# communication_module_20190819_to_aj-doy.net
KiCad netlist of a schematic drawn in EAGLE
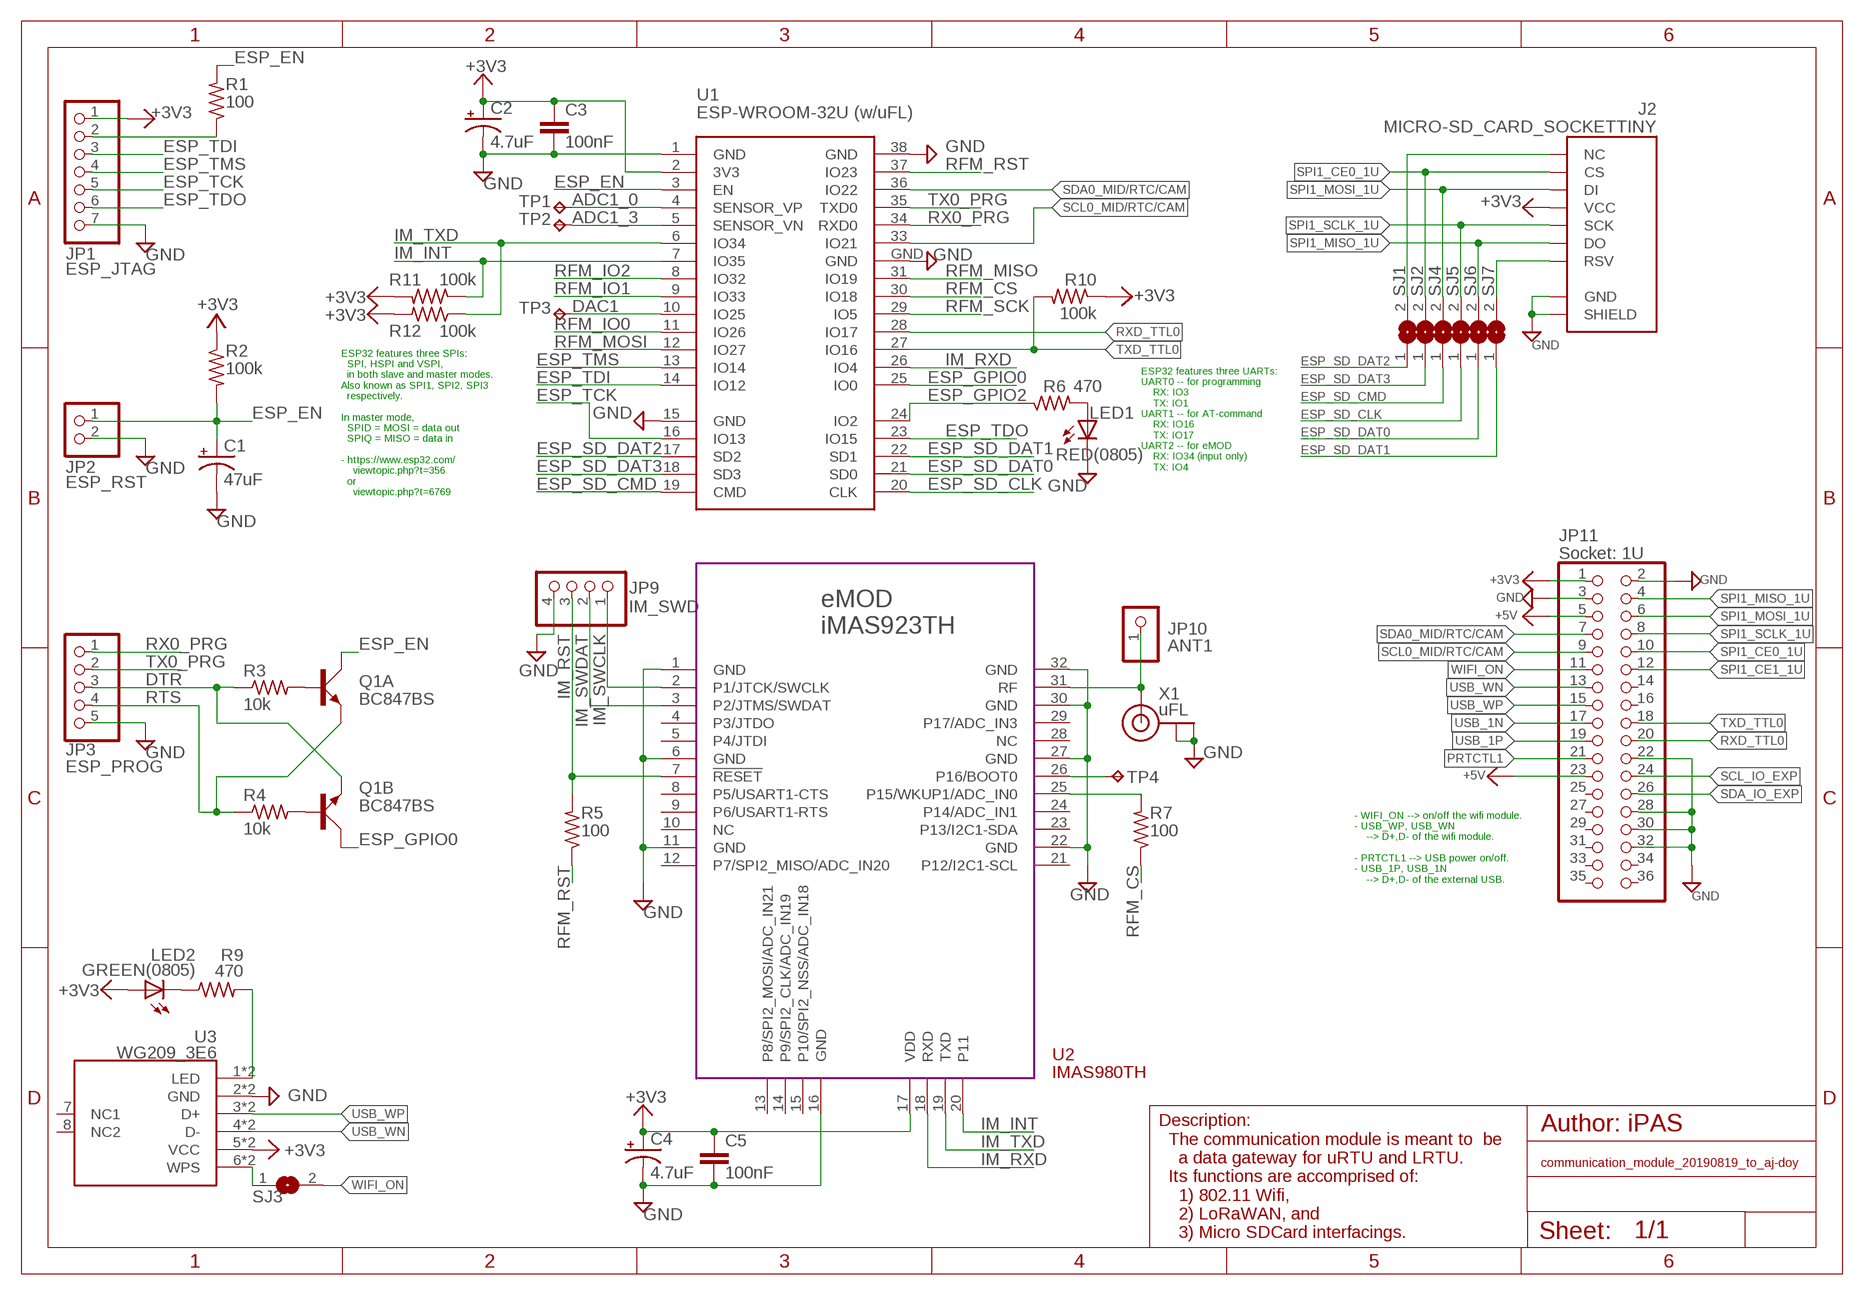
[diagram p0: schematic, sheet 1]

(export (version "E")
  (design (tool "Eeschema 10.0.6"))
  (components
    (comp (ref "C1")
      (value "47uF")
      (footprint "eagle-import:RCL_150CLZ-1014")
      (libsource (lib "eagle-import") (part "RCL_CPOL-US150CLZ-1014"))
    )
    (comp (ref "C2")
      (value "4.7uF")
      (footprint "eagle-import:RCL_150CLZ-1014")
      (libsource (lib "eagle-import") (part "RCL_CPOL-US150CLZ-1014"))
    )
    (comp (ref "C3")
      (value "100nF")
      (footprint "eagle-import:RCL_C1206")
      (libsource (lib "eagle-import") (part "RCL_C-EUC1206"))
    )
    (comp (ref "C4")
      (value "4.7uF")
      (footprint "eagle-import:RCL_150CLZ-1014")
      (libsource (lib "eagle-import") (part "RCL_CPOL-US150CLZ-1014"))
    )
    (comp (ref "C5")
      (value "100nF")
      (footprint "eagle-import:RCL_C1206")
      (libsource (lib "eagle-import") (part "RCL_C-EUC1206"))
    )
    (comp (ref "J2")
      (value "MICRO-SD_CARD_SOCKETTINY")
      (footprint "eagle-import:MICROSD_TINY")
      (libsource (lib "eagle-import") (part "MICRO-SD_CARD_SOCKETTINY"))
    )
    (comp (ref "JP1")
      (value "ESP_JTAG")
      (footprint "eagle-import:1X07")
      (libsource (lib "eagle-import") (part "PINHD-1X7"))
    )
    (comp (ref "JP2")
      (value "ESP_RST")
      (footprint "eagle-import:1X02")
      (libsource (lib "eagle-import") (part "PINHD-1X2"))
    )
    (comp (ref "JP3")
      (value "ESP_PROG")
      (footprint "eagle-import:1X05")
      (libsource (lib "eagle-import") (part "PINHD-1X5"))
    )
    (comp (ref "JP9")
      (value "IM_SWD")
      (footprint "eagle-import:1X04")
      (libsource (lib "eagle-import") (part "PINHD-1X4"))
    )
    (comp (ref "JP10")
      (value "ANT1")
      (footprint "eagle-import:1X01_ROUND")
      (libsource (lib "eagle-import") (part "HEADER-1X1ROUND"))
    )
    (comp (ref "JP11")
      (value "Socket: 1U")
      (footprint "eagle-import:2X18")
      (libsource (lib "eagle-import") (part "PINHD-2X18"))
    )
    (comp (ref "LED1")
      (value "RED(0805)")
      (footprint "eagle-import:CHIP-LED0805")
      (libsource (lib "eagle-import") (part "LEDCHIP-LED0805"))
    )
    (comp (ref "LED2")
      (value "GREEN(0805)")
      (footprint "eagle-import:CHIP-LED0805")
      (libsource (lib "eagle-import") (part "LEDCHIP-LED0805"))
    )
    (comp (ref "Q1")
      (value "BC847BS")
      (footprint "eagle-import:SOT363_PHILIPS")
      (libsource (lib "eagle-import") (part "BC847BS"))
    )
    (comp (ref "R1")
      (value "100")
      (footprint "eagle-import:RCL_M0805")
      (libsource (lib "eagle-import") (part "RCL_R-USM0805"))
    )
    (comp (ref "R2")
      (value "100k")
      (footprint "eagle-import:RCL_M0805")
      (libsource (lib "eagle-import") (part "RCL_R-USM0805"))
    )
    (comp (ref "R3")
      (value "10k")
      (footprint "eagle-import:RCL_M0805")
      (libsource (lib "eagle-import") (part "RCL_R-USM0805"))
    )
    (comp (ref "R4")
      (value "10k")
      (footprint "eagle-import:RCL_M0805")
      (libsource (lib "eagle-import") (part "RCL_R-USM0805"))
    )
    (comp (ref "R5")
      (value "100")
      (footprint "eagle-import:RCL_M0805")
      (libsource (lib "eagle-import") (part "RCL_R-USM0805"))
    )
    (comp (ref "R6")
      (value "470")
      (footprint "eagle-import:RCL_M0805")
      (libsource (lib "eagle-import") (part "RCL_R-USM0805"))
    )
    (comp (ref "R7")
      (value "100")
      (footprint "eagle-import:RCL_M0805")
      (libsource (lib "eagle-import") (part "RCL_R-USM0805"))
    )
    (comp (ref "R9")
      (value "470")
      (footprint "eagle-import:RCL_M0805")
      (libsource (lib "eagle-import") (part "RCL_R-USM0805"))
    )
    (comp (ref "R10")
      (value "100k")
      (footprint "eagle-import:RCL_M0805")
      (libsource (lib "eagle-import") (part "RCL_R-USM0805"))
    )
    (comp (ref "R11")
      (value "100k")
      (footprint "eagle-import:RCL_M0805")
      (libsource (lib "eagle-import") (part "RCL_R-USM0805"))
    )
    (comp (ref "R12")
      (value "100k")
      (footprint "eagle-import:RCL_M0805")
      (libsource (lib "eagle-import") (part "RCL_R-USM0805"))
    )
    (comp (ref "SJ1")
      (value "SOLDERJUMPERREFLOW")
      (footprint "eagle-import:SOLDERJUMPER_REFLOW")
      (libsource (lib "eagle-import") (part "SOLDERJUMPERREFLOW"))
    )
    (comp (ref "SJ2")
      (value "SOLDERJUMPERREFLOW")
      (footprint "eagle-import:SOLDERJUMPER_REFLOW")
      (libsource (lib "eagle-import") (part "SOLDERJUMPERREFLOW"))
    )
    (comp (ref "SJ3")
      (value "SOLDERJUMPERREFLOW")
      (footprint "eagle-import:SOLDERJUMPER_REFLOW")
      (libsource (lib "eagle-import") (part "SOLDERJUMPERREFLOW"))
    )
    (comp (ref "SJ4")
      (value "SOLDERJUMPERREFLOW")
      (footprint "eagle-import:SOLDERJUMPER_REFLOW")
      (libsource (lib "eagle-import") (part "SOLDERJUMPERREFLOW"))
    )
    (comp (ref "SJ5")
      (value "SOLDERJUMPERREFLOW")
      (footprint "eagle-import:SOLDERJUMPER_REFLOW")
      (libsource (lib "eagle-import") (part "SOLDERJUMPERREFLOW"))
    )
    (comp (ref "SJ6")
      (value "SOLDERJUMPERREFLOW")
      (footprint "eagle-import:SOLDERJUMPER_REFLOW")
      (libsource (lib "eagle-import") (part "SOLDERJUMPERREFLOW"))
    )
    (comp (ref "SJ7")
      (value "SOLDERJUMPERREFLOW")
      (footprint "eagle-import:SOLDERJUMPER_REFLOW")
      (libsource (lib "eagle-import") (part "SOLDERJUMPERREFLOW"))
    )
    (comp (ref "TP1")
      (value "TPB1,27")
      (footprint "eagle-import:B1,27")
      (libsource (lib "eagle-import") (part "TPB1,27"))
    )
    (comp (ref "TP2")
      (value "TPB1,27")
      (footprint "eagle-import:B1,27")
      (libsource (lib "eagle-import") (part "TPB1,27"))
    )
    (comp (ref "TP3")
      (value "TPB1,27")
      (footprint "eagle-import:B1,27")
      (libsource (lib "eagle-import") (part "TPB1,27"))
    )
    (comp (ref "TP4")
      (value "TPB1,27")
      (footprint "eagle-import:B1,27")
      (libsource (lib "eagle-import") (part "TPB1,27"))
    )
    (comp (ref "U1")
      (value "ESP-WROOM-32U (w/uFL)")
      (footprint "eagle-import:ESP-WROOM-32")
      (libsource (lib "eagle-import") (part "ESP-WROOM-32"))
    )
    (comp (ref "U2")
      (value "IMAS980TH")
      (footprint "eagle-import:IMAS923TH")
      (libsource (lib "eagle-import") (part "IMAS980TH"))
    )
    (comp (ref "U3")
      (value "WG209_3E6")
      (footprint "eagle-import:WG209")
      (libsource (lib "eagle-import") (part "WG209"))
    )
    (comp (ref "X1")
      (value "uFL")
      (footprint "eagle-import:U.FL")
      (libsource (lib "eagle-import") (part "ANTENNA_U.FL"))
    )
  )
  (nets
    (net (code "1") (name "+3V3") (class "Default")
      (node (ref "C2") (pin "+") (pinfunction "+_+") (pintype "passive"))
      (node (ref "C3") (pin "1") (pinfunction "1_1") (pintype "passive"))
      (node (ref "C4") (pin "+") (pinfunction "+_+") (pintype "passive"))
      (node (ref "C5") (pin "1") (pinfunction "1_1") (pintype "passive"))
      (node (ref "J2") (pin "4") (pinfunction "VCC_4") (pintype "bidirectional"))
      (node (ref "JP1") (pin "1") (pinfunction "1_1") (pintype "passive"))
      (node (ref "JP11") (pin "1") (pinfunction "1_1") (pintype "passive"))
      (node (ref "LED2") (pin "A") (pinfunction "A_A") (pintype "passive"))
      (node (ref "R10") (pin "1") (pinfunction "1_1") (pintype "passive"))
      (node (ref "R11") (pin "2") (pinfunction "2_2") (pintype "passive"))
      (node (ref "R12") (pin "2") (pinfunction "2_2") (pintype "passive"))
      (node (ref "R2") (pin "1") (pinfunction "1_1") (pintype "passive"))
      (node (ref "U1") (pin "2") (pinfunction "3V3_2") (pintype "power_in"))
      (node (ref "U2") (pin "17") (pinfunction "VDD_17") (pintype "power_in"))
      (node (ref "U3") (pin "5") (pinfunction "VCC_5") (pintype "power_in"))
      (node (ref "U3") (pin "5P") (pinfunction "VCC_5P") (pintype "power_in"))
    )
    (net (code "2") (name "+5V") (class "Default")
      (node (ref "JP11") (pin "23") (pinfunction "23_23") (pintype "passive"))
      (node (ref "JP11") (pin "5") (pinfunction "5_5") (pintype "passive"))
    )
    (net (code "3") (name "/ADC1_0") (class "Default")
      (node (ref "TP1") (pin "TP") (pinfunction "TP_TP") (pintype "input"))
      (node (ref "U1") (pin "4") (pinfunction "SENSOR_VP_4") (pintype "bidirectional"))
    )
    (net (code "4") (name "/ADC1_3") (class "Default")
      (node (ref "TP2") (pin "TP") (pinfunction "TP_TP") (pintype "input"))
      (node (ref "U1") (pin "5") (pinfunction "SENSOR_VN_5") (pintype "bidirectional"))
    )
    (net (code "5") (name "/DAC1") (class "Default")
      (node (ref "TP3") (pin "TP") (pinfunction "TP_TP") (pintype "input"))
      (node (ref "U1") (pin "10") (pinfunction "IO25_10") (pintype "bidirectional"))
    )
    (net (code "6") (name "/DTR") (class "Default")
      (node (ref "JP3") (pin "3") (pinfunction "3_3") (pintype "passive"))
      (node (ref "Q1") (pin "4") (pinfunction "E_4") (pintype "passive"))
      (node (ref "R3") (pin "1") (pinfunction "1_1") (pintype "passive"))
    )
    (net (code "7") (name "/ESP_EN") (class "Default")
      (node (ref "C1") (pin "+") (pinfunction "+_+") (pintype "passive"))
      (node (ref "JP2") (pin "1") (pinfunction "1_1") (pintype "passive"))
      (node (ref "Q1") (pin "6") (pinfunction "C_6") (pintype "passive"))
      (node (ref "R1") (pin "2") (pinfunction "2_2") (pintype "passive"))
      (node (ref "R2") (pin "2") (pinfunction "2_2") (pintype "passive"))
      (node (ref "U1") (pin "3") (pinfunction "EN_3") (pintype "input"))
    )
    (net (code "8") (name "/ESP_GPIO0") (class "Default")
      (node (ref "Q1") (pin "3") (pinfunction "C_3") (pintype "passive"))
      (node (ref "U1") (pin "25") (pinfunction "IO0_25") (pintype "bidirectional"))
    )
    (net (code "9") (name "/ESP_GPIO2") (class "Default")
      (node (ref "R6") (pin "1") (pinfunction "1_1") (pintype "passive"))
      (node (ref "U1") (pin "24") (pinfunction "IO2_24") (pintype "bidirectional"))
    )
    (net (code "10") (name "/ESP_SD_CLK") (class "Default")
      (node (ref "SJ5") (pin "1") (pinfunction "1_1") (pintype "passive"))
      (node (ref "U1") (pin "20") (pinfunction "CLK_20") (pintype "bidirectional"))
    )
    (net (code "11") (name "/ESP_SD_CMD") (class "Default")
      (node (ref "SJ4") (pin "1") (pinfunction "1_1") (pintype "passive"))
      (node (ref "U1") (pin "19") (pinfunction "CMD_19") (pintype "bidirectional"))
    )
    (net (code "12") (name "/ESP_SD_DAT0") (class "Default")
      (node (ref "SJ6") (pin "1") (pinfunction "1_1") (pintype "passive"))
      (node (ref "U1") (pin "21") (pinfunction "SD0_21") (pintype "bidirectional"))
    )
    (net (code "13") (name "/ESP_SD_DAT1") (class "Default")
      (node (ref "SJ7") (pin "1") (pinfunction "1_1") (pintype "passive"))
      (node (ref "U1") (pin "22") (pinfunction "SD1_22") (pintype "bidirectional"))
    )
    (net (code "14") (name "/ESP_SD_DAT2") (class "Default")
      (node (ref "SJ1") (pin "1") (pinfunction "1_1") (pintype "passive"))
      (node (ref "U1") (pin "17") (pinfunction "SD2_17") (pintype "bidirectional"))
    )
    (net (code "15") (name "/ESP_SD_DAT3") (class "Default")
      (node (ref "SJ2") (pin "1") (pinfunction "1_1") (pintype "passive"))
      (node (ref "U1") (pin "18") (pinfunction "SD3_18") (pintype "bidirectional"))
    )
    (net (code "16") (name "/ESP_TCK") (class "Default")
      (node (ref "JP1") (pin "5") (pinfunction "5_5") (pintype "passive"))
      (node (ref "U1") (pin "16") (pinfunction "IO13_16") (pintype "bidirectional"))
    )
    (net (code "17") (name "/ESP_TDI") (class "Default")
      (node (ref "JP1") (pin "3") (pinfunction "3_3") (pintype "passive"))
      (node (ref "U1") (pin "14") (pinfunction "IO12_14") (pintype "bidirectional"))
    )
    (net (code "18") (name "/ESP_TDO") (class "Default")
      (node (ref "JP1") (pin "6") (pinfunction "6_6") (pintype "passive"))
      (node (ref "U1") (pin "23") (pinfunction "IO15_23") (pintype "bidirectional"))
    )
    (net (code "19") (name "/ESP_TMS") (class "Default")
      (node (ref "JP1") (pin "4") (pinfunction "4_4") (pintype "passive"))
      (node (ref "U1") (pin "13") (pinfunction "IO14_13") (pintype "bidirectional"))
    )
    (net (code "20") (name "/IM_INT") (class "Default")
      (node (ref "R11") (pin "1") (pinfunction "1_1") (pintype "passive"))
      (node (ref "U1") (pin "7") (pinfunction "IO35_7") (pintype "bidirectional"))
      (node (ref "U2") (pin "20") (pinfunction "P11_20") (pintype "bidirectional"))
    )
    (net (code "21") (name "/IM_RST") (class "Default")
      (node (ref "JP9") (pin "3") (pinfunction "3_3") (pintype "passive"))
      (node (ref "R5") (pin "2") (pinfunction "2_2") (pintype "passive"))
      (node (ref "U2") (pin "7") (pinfunction "~{RESET}_7") (pintype "passive"))
    )
    (net (code "22") (name "/IM_RXD") (class "Default")
      (node (ref "U1") (pin "26") (pinfunction "IO4_26") (pintype "bidirectional"))
      (node (ref "U2") (pin "18") (pinfunction "RXD_18") (pintype "bidirectional"))
    )
    (net (code "23") (name "/IM_SWCLK") (class "Default")
      (node (ref "JP9") (pin "1") (pinfunction "1_1") (pintype "passive"))
      (node (ref "U2") (pin "2") (pinfunction "P1/JTCK/SWCLK_2") (pintype "bidirectional"))
    )
    (net (code "24") (name "/IM_SWDAT") (class "Default")
      (node (ref "JP9") (pin "2") (pinfunction "2_2") (pintype "passive"))
      (node (ref "U2") (pin "3") (pinfunction "P2/JTMS/SWDAT_3") (pintype "bidirectional"))
    )
    (net (code "25") (name "/IM_TXD") (class "Default")
      (node (ref "R12") (pin "1") (pinfunction "1_1") (pintype "passive"))
      (node (ref "U1") (pin "6") (pinfunction "IO34_6") (pintype "bidirectional"))
      (node (ref "U2") (pin "19") (pinfunction "TXD_19") (pintype "bidirectional"))
    )
    (net (code "26") (name "/RFM_CS") (class "Default")
      (node (ref "R7") (pin "1") (pinfunction "1_1") (pintype "passive"))
      (node (ref "U1") (pin "30") (pinfunction "IO18_30") (pintype "bidirectional"))
    )
    (net (code "27") (name "/RFM_IO0") (class "Default")
      (node (ref "U1") (pin "11") (pinfunction "IO26_11") (pintype "bidirectional"))
    )
    (net (code "28") (name "/RFM_IO1") (class "Default")
      (node (ref "U1") (pin "9") (pinfunction "IO33_9") (pintype "bidirectional"))
    )
    (net (code "29") (name "/RFM_IO2") (class "Default")
      (node (ref "U1") (pin "8") (pinfunction "IO32_8") (pintype "bidirectional"))
    )
    (net (code "30") (name "/RFM_MISO") (class "Default")
      (node (ref "U1") (pin "31") (pinfunction "IO19_31") (pintype "bidirectional"))
    )
    (net (code "31") (name "/RFM_MOSI") (class "Default")
      (node (ref "U1") (pin "12") (pinfunction "IO27_12") (pintype "bidirectional"))
    )
    (net (code "32") (name "/RFM_RST") (class "Default")
      (node (ref "R5") (pin "1") (pinfunction "1_1") (pintype "passive"))
      (node (ref "U1") (pin "37") (pinfunction "IO23_37") (pintype "bidirectional"))
    )
    (net (code "33") (name "/RFM_SCK") (class "Default")
      (node (ref "U1") (pin "29") (pinfunction "IO5_29") (pintype "bidirectional"))
    )
    (net (code "34") (name "/RTS") (class "Default")
      (node (ref "JP3") (pin "4") (pinfunction "4_4") (pintype "passive"))
      (node (ref "Q1") (pin "1") (pinfunction "E_1") (pintype "passive"))
      (node (ref "R4") (pin "1") (pinfunction "1_1") (pintype "passive"))
    )
    (net (code "35") (name "/RX0_PRG") (class "Default")
      (node (ref "JP3") (pin "1") (pinfunction "1_1") (pintype "passive"))
      (node (ref "U1") (pin "34") (pinfunction "RXD0_34") (pintype "bidirectional"))
    )
    (net (code "36") (name "/TX0_PRG") (class "Default")
      (node (ref "JP3") (pin "2") (pinfunction "2_2") (pintype "passive"))
      (node (ref "U1") (pin "35") (pinfunction "TXD0_35") (pintype "bidirectional"))
    )
    (net (code "37") (name "GND") (class "Default")
      (node (ref "C1") (pin "-") (pinfunction "-_-") (pintype "passive"))
      (node (ref "C2") (pin "-") (pinfunction "-_-") (pintype "passive"))
      (node (ref "C3") (pin "2") (pinfunction "2_2") (pintype "passive"))
      (node (ref "C4") (pin "-") (pinfunction "-_-") (pintype "passive"))
      (node (ref "C5") (pin "2") (pinfunction "2_2") (pintype "passive"))
      (node (ref "J2") (pin "6") (pinfunction "GND_6") (pintype "bidirectional"))
      (node (ref "J2") (pin "GND1") (pinfunction "SHIELD_GND1") (pintype "bidirectional"))
      (node (ref "J2") (pin "GND2") (pinfunction "SHIELD_GND2") (pintype "bidirectional"))
      (node (ref "J2") (pin "GND3") (pinfunction "SHIELD_GND3") (pintype "bidirectional"))
      (node (ref "J2") (pin "GND4") (pinfunction "SHIELD_GND4") (pintype "bidirectional"))
      (node (ref "J2") (pin "GND5") (pinfunction "SHIELD_GND5") (pintype "bidirectional"))
      (node (ref "J2") (pin "GND6") (pinfunction "SHIELD_GND6") (pintype "bidirectional"))
      (node (ref "JP1") (pin "7") (pinfunction "7_7") (pintype "passive"))
      (node (ref "JP11") (pin "2") (pinfunction "2_2") (pintype "passive"))
      (node (ref "JP11") (pin "22") (pinfunction "22_22") (pintype "passive"))
      (node (ref "JP11") (pin "28") (pinfunction "28_28") (pintype "passive"))
      (node (ref "JP11") (pin "3") (pinfunction "3_3") (pintype "passive"))
      (node (ref "JP11") (pin "30") (pinfunction "30_30") (pintype "passive"))
      (node (ref "JP11") (pin "32") (pinfunction "32_32") (pintype "passive"))
      (node (ref "JP2") (pin "2") (pinfunction "2_2") (pintype "passive"))
      (node (ref "JP3") (pin "5") (pinfunction "5_5") (pintype "passive"))
      (node (ref "JP9") (pin "4") (pinfunction "4_4") (pintype "passive"))
      (node (ref "LED1") (pin "C") (pinfunction "C_C") (pintype "passive"))
      (node (ref "U1") (pin "1") (pinfunction "GND_1") (pintype "power_in"))
      (node (ref "U1") (pin "15") (pinfunction "GND_15") (pintype "power_in"))
      (node (ref "U1") (pin "38") (pinfunction "GND_38") (pintype "power_in"))
      (node (ref "U1") (pin "GND") (pinfunction "GND_GND") (pintype "power_in"))
      (node (ref "U2") (pin "1") (pinfunction "GND_1") (pintype "power_in"))
      (node (ref "U2") (pin "11") (pinfunction "GND_11") (pintype "power_in"))
      (node (ref "U2") (pin "16") (pinfunction "GND_16") (pintype "power_in"))
      (node (ref "U2") (pin "22") (pinfunction "GND_22") (pintype "power_in"))
      (node (ref "U2") (pin "27") (pinfunction "GND_27") (pintype "power_in"))
      (node (ref "U2") (pin "30") (pinfunction "GND_30") (pintype "power_in"))
      (node (ref "U2") (pin "32") (pinfunction "GND_32") (pintype "power_in"))
      (node (ref "U2") (pin "6") (pinfunction "GND_6") (pintype "power_in"))
      (node (ref "U3") (pin "2") (pinfunction "GND_2") (pintype "power_in"))
      (node (ref "U3") (pin "2P") (pinfunction "GND_2P") (pintype "power_in"))
      (node (ref "X1") (pin "1") (pinfunction "GND_1") (pintype "passive"))
      (node (ref "X1") (pin "2") (pinfunction "GND_2") (pintype "passive"))
    )
    (net (code "38") (name "Net-(J2-NC)") (class "Default")
      (node (ref "J2") (pin "9") (pinfunction "NC_9") (pintype "bidirectional"))
      (node (ref "SJ1") (pin "2") (pinfunction "2_2") (pintype "passive"))
    )
    (net (code "39") (name "Net-(J2-RSV-Pad1)") (class "Default")
      (node (ref "J2") (pin "1") (pinfunction "RSV_1") (pintype "bidirectional"))
      (node (ref "J2") (pin "8") (pinfunction "RSV_8") (pintype "bidirectional"))
      (node (ref "SJ7") (pin "2") (pinfunction "2_2") (pintype "passive"))
    )
    (net (code "40") (name "Net-(JP1-Pad2)") (class "Default")
      (node (ref "JP1") (pin "2") (pinfunction "2_2") (pintype "passive"))
      (node (ref "R1") (pin "1") (pinfunction "1_1") (pintype "passive"))
    )
    (net (code "41") (name "Net-(LED1-PadA)") (class "Default")
      (node (ref "LED1") (pin "A") (pinfunction "A_A") (pintype "passive"))
      (node (ref "R6") (pin "2") (pinfunction "2_2") (pintype "passive"))
    )
    (net (code "42") (name "Net-(LED2-PadC)") (class "Default")
      (node (ref "LED2") (pin "C") (pinfunction "C_C") (pintype "passive"))
      (node (ref "R9") (pin "1") (pinfunction "1_1") (pintype "passive"))
    )
    (net (code "43") (name "Net-(Q1A-B)") (class "Default")
      (node (ref "Q1") (pin "2") (pinfunction "B_2") (pintype "passive"))
      (node (ref "R3") (pin "2") (pinfunction "2_2") (pintype "passive"))
    )
    (net (code "44") (name "Net-(Q1B-B)") (class "Default")
      (node (ref "Q1") (pin "5") (pinfunction "B_5") (pintype "passive"))
      (node (ref "R4") (pin "2") (pinfunction "2_2") (pintype "passive"))
    )
    (net (code "45") (name "Net-(R9-Pad2)") (class "Default")
      (node (ref "R9") (pin "2") (pinfunction "2_2") (pintype "passive"))
      (node (ref "U3") (pin "1") (pinfunction "LED_1") (pintype "bidirectional"))
      (node (ref "U3") (pin "1P") (pinfunction "LED_1P") (pintype "bidirectional"))
    )
    (net (code "46") (name "Net-(SJ3-Pad1)") (class "Default")
      (node (ref "SJ3") (pin "1") (pinfunction "1_1") (pintype "passive"))
      (node (ref "U3") (pin "6") (pinfunction "WPS_6") (pintype "bidirectional"))
      (node (ref "U3") (pin "6P") (pinfunction "WPS_6P") (pintype "bidirectional"))
    )
    (net (code "47") (name "Net-(U2-P15{slash}WKUP1{slash}ADC_IN0)") (class "Default")
      (node (ref "R7") (pin "2") (pinfunction "2_2") (pintype "passive"))
      (node (ref "U2") (pin "25") (pinfunction "P15/WKUP1/ADC_IN0_25") (pintype "bidirectional"))
    )
    (net (code "48") (name "Net-(U2-P16{slash}BOOT0)") (class "Default")
      (node (ref "TP4") (pin "TP") (pinfunction "TP_TP") (pintype "input"))
      (node (ref "U2") (pin "26") (pinfunction "P16/BOOT0_26") (pintype "passive"))
    )
    (net (code "49") (name "Net-(U2-RF)") (class "Default")
      (node (ref "JP10") (pin "1") (pinfunction "1_1") (pintype "passive"))
      (node (ref "U2") (pin "31") (pinfunction "RF_31") (pintype "bidirectional"))
      (node (ref "X1") (pin "3") (pinfunction "SIGNAL_3") (pintype "passive"))
    )
    (net (code "50") (name "PRTCTL1") (class "Default")
      (node (ref "JP11") (pin "21") (pinfunction "21_21") (pintype "passive"))
    )
    (net (code "51") (name "RXD_TTL0") (class "Default")
      (node (ref "JP11") (pin "20") (pinfunction "20_20") (pintype "passive"))
      (node (ref "U1") (pin "28") (pinfunction "IO17_28") (pintype "bidirectional"))
    )
    (net (code "52") (name "SCL0_MID{slash}RTC{slash}CAM") (class "Default")
      (node (ref "JP11") (pin "9") (pinfunction "9_9") (pintype "passive"))
      (node (ref "U1") (pin "33") (pinfunction "IO21_33") (pintype "bidirectional"))
    )
    (net (code "53") (name "SCL_IO_EXP") (class "Default")
      (node (ref "JP11") (pin "24") (pinfunction "24_24") (pintype "passive"))
    )
    (net (code "54") (name "SDA0_MID{slash}RTC{slash}CAM") (class "Default")
      (node (ref "JP11") (pin "7") (pinfunction "7_7") (pintype "passive"))
      (node (ref "U1") (pin "36") (pinfunction "IO22_36") (pintype "bidirectional"))
    )
    (net (code "55") (name "SDA_IO_EXP") (class "Default")
      (node (ref "JP11") (pin "26") (pinfunction "26_26") (pintype "passive"))
    )
    (net (code "56") (name "SPI1_CE0_1U") (class "Default")
      (node (ref "J2") (pin "2") (pinfunction "CS_2") (pintype "bidirectional"))
      (node (ref "JP11") (pin "10") (pinfunction "10_10") (pintype "passive"))
      (node (ref "SJ2") (pin "2") (pinfunction "2_2") (pintype "passive"))
    )
    (net (code "57") (name "SPI1_CE1_1U") (class "Default")
      (node (ref "JP11") (pin "12") (pinfunction "12_12") (pintype "passive"))
    )
    (net (code "58") (name "SPI1_MISO_1U") (class "Default")
      (node (ref "J2") (pin "7") (pinfunction "DO_7") (pintype "bidirectional"))
      (node (ref "JP11") (pin "4") (pinfunction "4_4") (pintype "passive"))
      (node (ref "SJ6") (pin "2") (pinfunction "2_2") (pintype "passive"))
    )
    (net (code "59") (name "SPI1_MOSI_1U") (class "Default")
      (node (ref "J2") (pin "3") (pinfunction "DI_3") (pintype "bidirectional"))
      (node (ref "JP11") (pin "6") (pinfunction "6_6") (pintype "passive"))
      (node (ref "SJ4") (pin "2") (pinfunction "2_2") (pintype "passive"))
    )
    (net (code "60") (name "SPI1_SCLK_1U") (class "Default")
      (node (ref "J2") (pin "5") (pinfunction "SCK_5") (pintype "bidirectional"))
      (node (ref "JP11") (pin "8") (pinfunction "8_8") (pintype "passive"))
      (node (ref "SJ5") (pin "2") (pinfunction "2_2") (pintype "passive"))
    )
    (net (code "61") (name "TXD_TTL0") (class "Default")
      (node (ref "JP11") (pin "18") (pinfunction "18_18") (pintype "passive"))
      (node (ref "R10") (pin "2") (pinfunction "2_2") (pintype "passive"))
      (node (ref "U1") (pin "27") (pinfunction "IO16_27") (pintype "bidirectional"))
    )
    (net (code "62") (name "USB_1N") (class "Default")
      (node (ref "JP11") (pin "17") (pinfunction "17_17") (pintype "passive"))
    )
    (net (code "63") (name "USB_1P") (class "Default")
      (node (ref "JP11") (pin "19") (pinfunction "19_19") (pintype "passive"))
    )
    (net (code "64") (name "USB_WN") (class "Default")
      (node (ref "JP11") (pin "13") (pinfunction "13_13") (pintype "passive"))
      (node (ref "U3") (pin "4") (pinfunction "D-_4") (pintype "bidirectional"))
      (node (ref "U3") (pin "4P") (pinfunction "D-_4P") (pintype "bidirectional"))
    )
    (net (code "65") (name "USB_WP") (class "Default")
      (node (ref "JP11") (pin "15") (pinfunction "15_15") (pintype "passive"))
      (node (ref "U3") (pin "3") (pinfunction "D+_3") (pintype "bidirectional"))
      (node (ref "U3") (pin "3P") (pinfunction "D+_3P") (pintype "bidirectional"))
    )
    (net (code "66") (name "WIFI_ON") (class "Default")
      (node (ref "JP11") (pin "11") (pinfunction "11_11") (pintype "passive"))
      (node (ref "SJ3") (pin "2") (pinfunction "2_2") (pintype "passive"))
    )
    (net (code "67") (name "unconnected-(JP11-Pad14)") (class "Default")
      (node (ref "JP11") (pin "14") (pinfunction "14_14") (pintype "passive"))
    )
    (net (code "68") (name "unconnected-(JP11-Pad16)") (class "Default")
      (node (ref "JP11") (pin "16") (pinfunction "16_16") (pintype "passive"))
    )
    (net (code "69") (name "unconnected-(JP11-Pad25)") (class "Default")
      (node (ref "JP11") (pin "25") (pinfunction "25_25") (pintype "passive"))
    )
    (net (code "70") (name "unconnected-(JP11-Pad27)") (class "Default")
      (node (ref "JP11") (pin "27") (pinfunction "27_27") (pintype "passive"))
    )
    (net (code "71") (name "unconnected-(JP11-Pad29)") (class "Default")
      (node (ref "JP11") (pin "29") (pinfunction "29_29") (pintype "passive"))
    )
    (net (code "72") (name "unconnected-(JP11-Pad31)") (class "Default")
      (node (ref "JP11") (pin "31") (pinfunction "31_31") (pintype "passive"))
    )
    (net (code "73") (name "unconnected-(JP11-Pad33)") (class "Default")
      (node (ref "JP11") (pin "33") (pinfunction "33_33") (pintype "passive"))
    )
    (net (code "74") (name "unconnected-(JP11-Pad34)") (class "Default")
      (node (ref "JP11") (pin "34") (pinfunction "34_34") (pintype "passive"))
    )
    (net (code "75") (name "unconnected-(JP11-Pad35)") (class "Default")
      (node (ref "JP11") (pin "35") (pinfunction "35_35") (pintype "passive"))
    )
    (net (code "76") (name "unconnected-(JP11-Pad36)") (class "Default")
      (node (ref "JP11") (pin "36") (pinfunction "36_36") (pintype "passive"))
    )
    (net (code "77") (name "unconnected-(U2-NC-Pad10)") (class "Default")
      (node (ref "U2") (pin "10") (pinfunction "NC_10") (pintype "no_connect"))
    )
    (net (code "78") (name "unconnected-(U2-NC-Pad28)") (class "Default")
      (node (ref "U2") (pin "28") (pinfunction "NC_28") (pintype "no_connect"))
    )
    (net (code "79") (name "unconnected-(U2-P3{slash}JTDO-Pad4)") (class "Default")
      (node (ref "U2") (pin "4") (pinfunction "P3/JTDO_4") (pintype "bidirectional"))
    )
    (net (code "80") (name "unconnected-(U2-P4{slash}JTDI-Pad5)") (class "Default")
      (node (ref "U2") (pin "5") (pinfunction "P4/JTDI_5") (pintype "bidirectional"))
    )
    (net (code "81") (name "unconnected-(U2-P5{slash}USART1-CTS-Pad8)") (class "Default")
      (node (ref "U2") (pin "8") (pinfunction "P5/USART1-CTS_8") (pintype "bidirectional"))
    )
    (net (code "82") (name "unconnected-(U2-P6{slash}USART1-RTS-Pad9)") (class "Default")
      (node (ref "U2") (pin "9") (pinfunction "P6/USART1-RTS_9") (pintype "bidirectional"))
    )
    (net (code "83") (name "unconnected-(U2-P7{slash}SPI2_MISO{slash}ADC_IN20-Pad12)") (class "Default")
      (node (ref "U2") (pin "12") (pinfunction "P7/SPI2_MISO/ADC_IN20_12") (pintype "bidirectional"))
    )
    (net (code "84") (name "unconnected-(U2-P8{slash}SPI2_MOSI{slash}ADC_IN21-Pad13)") (class "Default")
      (node (ref "U2") (pin "13") (pinfunction "P8/SPI2_MOSI/ADC_IN21_13") (pintype "bidirectional"))
    )
    (net (code "85") (name "unconnected-(U2-P9{slash}SPI2_CLK{slash}ADC_IN19-Pad14)") (class "Default")
      (node (ref "U2") (pin "14") (pinfunction "P9/SPI2_CLK/ADC_IN19_14") (pintype "bidirectional"))
    )
    (net (code "86") (name "unconnected-(U2-P10{slash}SPI2_NSS{slash}ADC_IN18-Pad15)") (class "Default")
      (node (ref "U2") (pin "15") (pinfunction "P10/SPI2_NSS/ADC_IN18_15") (pintype "bidirectional"))
    )
    (net (code "87") (name "unconnected-(U2-P12{slash}I2C1-SCL-Pad21)") (class "Default")
      (node (ref "U2") (pin "21") (pinfunction "P12/I2C1-SCL_21") (pintype "bidirectional"))
    )
    (net (code "88") (name "unconnected-(U2-P13{slash}I2C1-SDA-Pad23)") (class "Default")
      (node (ref "U2") (pin "23") (pinfunction "P13/I2C1-SDA_23") (pintype "bidirectional"))
    )
    (net (code "89") (name "unconnected-(U2-P14{slash}ADC_IN1-Pad24)") (class "Default")
      (node (ref "U2") (pin "24") (pinfunction "P14/ADC_IN1_24") (pintype "bidirectional"))
    )
    (net (code "90") (name "unconnected-(U2-P17{slash}ADC_IN3-Pad29)") (class "Default")
      (node (ref "U2") (pin "29") (pinfunction "P17/ADC_IN3_29") (pintype "bidirectional"))
    )
    (net (code "91") (name "unconnected-(U3-NC1-Pad7)") (class "Default")
      (node (ref "U3") (pin "7") (pinfunction "NC1_7") (pintype "no_connect"))
    )
    (net (code "92") (name "unconnected-(U3-NC2-Pad8)") (class "Default")
      (node (ref "U3") (pin "8") (pinfunction "NC2_8") (pintype "no_connect"))
    )
  )
)
